# BAT_POWER.net
KiCad netlist of a schematic drawn in Altium Designer
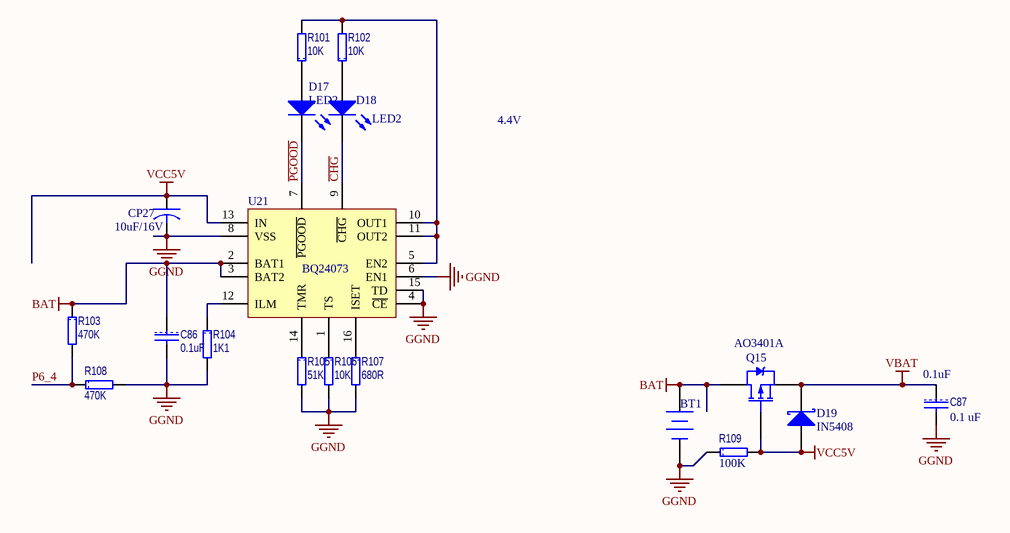
[diagram p0: BAT POWER.SchDoc]

(export (version "E")
  (design (tool "Eeschema 10.0.6"))
  (components
    (comp (ref "BT1")
      (value "Battery")
      (footprint "BAT-2")
      (description "插针 Multicell Battery")
      (fields (field (name "PUBLISHER") "Altium Limited"))
      (libsource (lib "*") (part "Battery"))
    )
    (comp (ref "C86")
      (value "0.1uF")
      (footprint "1608[0603]")
      (description "Capacitor")
      (fields (field (name "MANUFACTURER") "TDK"))
      (libsource (lib "*") (part "CAP"))
    )
    (comp (ref "C87")
      (value "0.1uF")
      (footprint "1608[0603]C")
      (description "多层陶瓷电容器MLCC - SMD/SMT 0603 0.1uF 50volts X7R 10%")
      (fields
        (field (name "MANUFACTURER") "TDK")
        (field (name "MANUFACTURER PART NUMBER") "C1608X7R1H104K")
        (field (name "ΜÇÈÝ") "0.1 uF")
      )
      (libsource (lib "*") (part "CAP"))
    )
    (comp (ref "CP27")
      (value "10uF/16V")
      (footprint "3216[1206]")
      (description "Tantalum Capacitor")
      (libsource (lib "*") (part "CAPACITOR"))
    )
    (comp (ref "D17")
      (value "LED2")
      (footprint "0805LED")
      (description "Typical RED, GREEN, YELLOW, AMBER GaAs LED")
      (fields (field (name "PUBLISHER") "Altium Limited"))
      (libsource (lib "Miscellaneous Devices") (part "LED2"))
    )
    (comp (ref "D18")
      (value "LED2")
      (footprint "0805LED")
      (description "Typical RED, GREEN, YELLOW, AMBER GaAs LED")
      (fields (field (name "PUBLISHER") "Altium Limited"))
      (libsource (lib "Miscellaneous Devices") (part "LED2"))
    )
    (comp (ref "D19")
      (value "IN5408")
      (footprint "2440PCBV5:DO-214AB/SMC")
      (description "肖特基二极管与整流器 3.0 Amp 60 Volt")
      (fields
        (field (name "MANUFACTURER") "Vishay Semiconductors")
        (field (name "MANUFACTURER PART NUMBER") "SS36-E3/57T")
      )
      (libsource (lib "Miscellaneous Devices") (part "D Schottky"))
    )
    (comp (ref "Q15")
      (value "AO3401A")
      (footprint "SOT23_N")
      (description "MOSFET P-CH -30V -4.3A SOT23")
      (fields (field (name "MANUFACTURER") "Alpha & Omega Semiconductor Inc"))
      (libsource (lib "IR Discrete MOSFET - Power") (part "IRLML5103"))
    )
    (comp (ref "R101")
      (value "10K")
      (footprint "1608[0603]R")
      (description "RES")
      (libsource (lib "*") (part "RES"))
    )
    (comp (ref "R102")
      (value "10K")
      (footprint "1608[0603]R")
      (description "RES")
      (libsource (lib "*") (part "RES"))
    )
    (comp (ref "R103")
      (value "470K")
      (footprint "1608[0603]R")
      (description "RES")
      (fields (field (name "MANUFACTURER") "vishay"))
      (libsource (lib "*") (part "RES"))
    )
    (comp (ref "R104")
      (value "1K1")
      (footprint "1608[0603]R")
      (description "RES")
      (fields (field (name "MANUFACTURER") "vishay"))
      (libsource (lib "*") (part "RES"))
    )
    (comp (ref "R105")
      (value "51K")
      (footprint "1608[0603]R")
      (description "RES")
      (fields (field (name "MANUFACTURER") "vishay"))
      (libsource (lib "*") (part "RES"))
    )
    (comp (ref "R106")
      (value "10K")
      (footprint "1608[0603]R")
      (description "RES")
      (fields (field (name "MANUFACTURER") "vishay"))
      (libsource (lib "*") (part "RES"))
    )
    (comp (ref "R107")
      (value "680R")
      (footprint "1608[0603]R")
      (description "RES")
      (fields (field (name "MANUFACTURER") "vishay"))
      (libsource (lib "*") (part "RES"))
    )
    (comp (ref "R108")
      (value "470K")
      (footprint "1608[0603]R")
      (description "RES")
      (fields (field (name "MANUFACTURER") "vishay"))
      (libsource (lib "*") (part "RES"))
    )
    (comp (ref "R109")
      (value "100K")
      (footprint "1608[0603]R")
      (description "厚膜电阻器 - SMD 1/10watt 100Kohms 1%")
      (fields
        (field (name "MANUFACTURER") "Vishay / Dale")
        (field (name "MANUFACTURER PART NUMBER") "CRCW0603100KFKEA")
      )
      (libsource (lib "100K 1%") (part "RES"))
    )
    (comp (ref "U21") (value "BQ24073") (footprint "BQ24073") (libsource (lib "*") (part "BQ24073")))
  )
  (nets
    (net (code "1") (name "/P6_4") (class "Default")
      (node (ref "R103") (pin "2") (pinfunction "2_2") (pintype "passive"))
      (node (ref "R108") (pin "1") (pinfunction "1_1") (pintype "passive"))
    )
    (net (code "2") (name "/~{CHG}") (class "Default")
      (node (ref "D18") (pin "2") (pinfunction "K_2") (pintype "passive"))
      (node (ref "U21") (pin "9") (pinfunction "~{CHG}_9") (pintype "passive"))
    )
    (net (code "3") (name "/~{PGOOD}") (class "Default")
      (node (ref "D17") (pin "2") (pinfunction "K_2") (pintype "passive"))
      (node (ref "U21") (pin "7") (pinfunction "~{PGOOD}_7") (pintype "passive"))
    )
    (net (code "4") (name "BAT") (class "Default")
      (node (ref "BT1") (pin "1") (pinfunction "+_1") (pintype "passive"))
      (node (ref "C86") (pin "1") (pinfunction "1_1") (pintype "passive"))
      (node (ref "Q15") (pin "3") (pinfunction "D_3") (pintype "passive"))
      (node (ref "R103") (pin "1") (pinfunction "1_1") (pintype "passive"))
      (node (ref "U21") (pin "2") (pinfunction "BAT1_2") (pintype "passive"))
      (node (ref "U21") (pin "3") (pinfunction "BAT2_3") (pintype "passive"))
    )
    (net (code "5") (name "GGND") (class "Default")
      (node (ref "BT1") (pin "2") (pinfunction "-_2") (pintype "passive"))
      (node (ref "C86") (pin "2") (pinfunction "2_2") (pintype "passive"))
      (node (ref "C87") (pin "2") (pinfunction "2_2") (pintype "passive"))
      (node (ref "CP27") (pin "2") (pinfunction "2_2") (pintype "passive"))
      (node (ref "R104") (pin "2") (pinfunction "2_2") (pintype "passive"))
      (node (ref "R105") (pin "2") (pinfunction "2_2") (pintype "passive"))
      (node (ref "R106") (pin "2") (pinfunction "2_2") (pintype "passive"))
      (node (ref "R107") (pin "2") (pinfunction "2_2") (pintype "passive"))
      (node (ref "R108") (pin "2") (pinfunction "2_2") (pintype "passive"))
      (node (ref "R109") (pin "1") (pinfunction "1_1") (pintype "passive"))
      (node (ref "U21") (pin "15") (pinfunction "TD_15") (pintype "passive"))
      (node (ref "U21") (pin "4") (pinfunction "~{CE}_4") (pintype "passive"))
      (node (ref "U21") (pin "6") (pinfunction "EN1_6") (pintype "passive"))
      (node (ref "U21") (pin "8") (pinfunction "VSS_8") (pintype "passive"))
    )
    (net (code "6") (name "Net-(D17-A)") (class "Default")
      (node (ref "D17") (pin "1") (pinfunction "A_1") (pintype "passive"))
      (node (ref "R101") (pin "1") (pinfunction "1_1") (pintype "passive"))
    )
    (net (code "7") (name "Net-(D18-A)") (class "Default")
      (node (ref "D18") (pin "1") (pinfunction "A_1") (pintype "passive"))
      (node (ref "R102") (pin "1") (pinfunction "1_1") (pintype "passive"))
    )
    (net (code "8") (name "Net-(U21-EN2)") (class "Default")
      (node (ref "R101") (pin "2") (pinfunction "2_2") (pintype "passive"))
      (node (ref "R102") (pin "2") (pinfunction "2_2") (pintype "passive"))
      (node (ref "U21") (pin "10") (pinfunction "OUT1_10") (pintype "passive"))
      (node (ref "U21") (pin "11") (pinfunction "OUT2_11") (pintype "passive"))
      (node (ref "U21") (pin "5") (pinfunction "EN2_5") (pintype "passive"))
    )
    (net (code "9") (name "Net-(U21-ILM)") (class "Default")
      (node (ref "R104") (pin "1") (pinfunction "1_1") (pintype "passive"))
      (node (ref "U21") (pin "12") (pinfunction "ILM_12") (pintype "passive"))
    )
    (net (code "10") (name "Net-(U21-ISET)") (class "Default")
      (node (ref "R107") (pin "1") (pinfunction "1_1") (pintype "passive"))
      (node (ref "U21") (pin "16") (pinfunction "ISET_16") (pintype "passive"))
    )
    (net (code "11") (name "Net-(U21-TMR)") (class "Default")
      (node (ref "R105") (pin "1") (pinfunction "1_1") (pintype "passive"))
      (node (ref "U21") (pin "14") (pinfunction "TMR_14") (pintype "passive"))
    )
    (net (code "12") (name "Net-(U21-TS)") (class "Default")
      (node (ref "R106") (pin "1") (pinfunction "1_1") (pintype "passive"))
      (node (ref "U21") (pin "1") (pinfunction "TS_1") (pintype "passive"))
    )
    (net (code "13") (name "VBAT") (class "Default")
      (node (ref "C87") (pin "1") (pinfunction "1_1") (pintype "passive"))
      (node (ref "D19") (pin "2") (pinfunction "K_2") (pintype "passive"))
      (node (ref "Q15") (pin "2") (pinfunction "S_2") (pintype "passive"))
    )
    (net (code "14") (name "VCC5V") (class "Default")
      (node (ref "CP27") (pin "1") (pinfunction "1_1") (pintype "passive"))
      (node (ref "D19") (pin "1") (pinfunction "A_1") (pintype "passive"))
      (node (ref "Q15") (pin "1") (pinfunction "G_1") (pintype "passive"))
      (node (ref "R109") (pin "2") (pinfunction "2_2") (pintype "passive"))
      (node (ref "U21") (pin "13") (pinfunction "IN_13") (pintype "passive"))
    )
  )
)
